# CPU_AV.net
KiCad netlist of a schematic drawn in Altium Designer
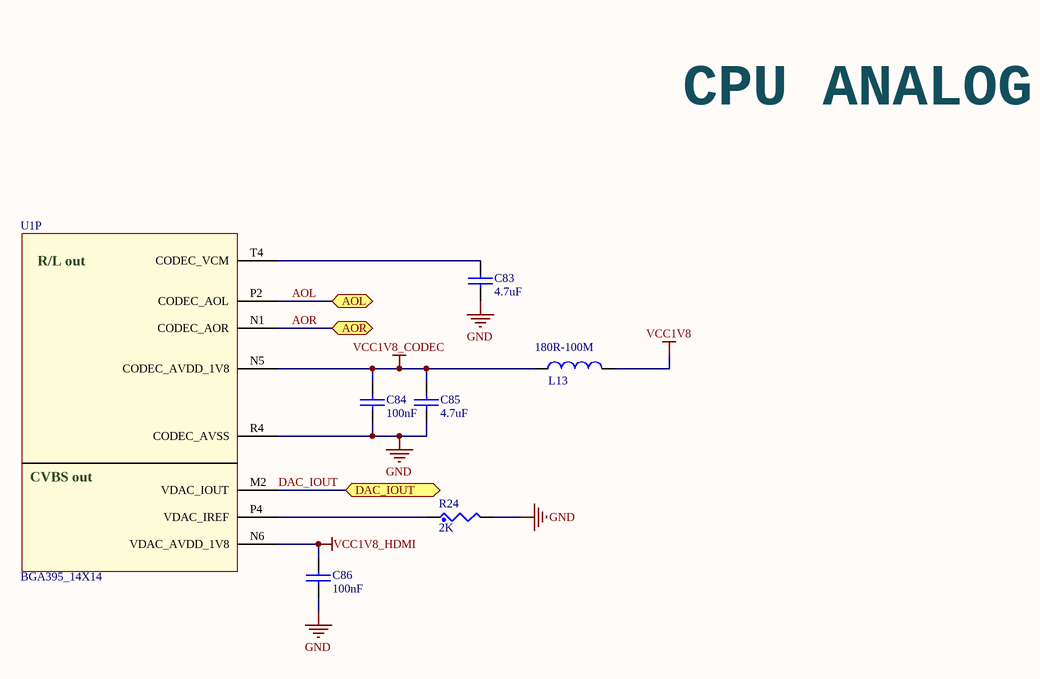
[diagram p0: CPU_AV.SchDoc]

(export (version "E")
  (design (tool "Eeschema 10.0.6"))
  (components
    (comp (ref "C83")
      (value "4.7uF")
      (footprint "0402_CC - C")
      (libsource (lib "AAR_RockChip_RK3328") (part "CAP_NP"))
    )
    (comp (ref "C84")
      (value "100nF")
      (footprint "0402_CC - C")
      (libsource (lib "AAR_RockChip_RK3328") (part "CAP_NP"))
    )
    (comp (ref "C85")
      (value "4.7uF")
      (footprint "0402_CC - C")
      (libsource (lib "AAR_RockChip_RK3328") (part "CAP_NP"))
    )
    (comp (ref "C86")
      (value "100nF")
      (footprint "0402_CC - C")
      (libsource (lib "AAR_RockChip_RK3328") (part "CAP_NP"))
    )
    (comp (ref "L13")
      (value "180R-100M")
      (footprint "0603_C_Inductor")
      (description "Fixed Inductors  TDK, By AAR")
      (libsource (lib "AAR_RockChip_RK3328") (part "INDCHIP"))
    )
    (comp (ref "R24") (value "2K") (footprint "0402_CR") (libsource (lib "AAR_RockChip_RK3328") (part "RES")))
    (comp (ref "U1")
      (value "BGA395_14X14")
      (footprint "BGA395C65P21X21_1750X1750X117")
      (description "By AAR")
      (libsource (lib "AAR_RockChip_RK3328") (part "RK3328"))
    )
  )
  (nets
    (net (code "1") (name "/AOL") (class "Default")
      (node (ref "U1") (pin "P2") (pinfunction "CODEC_AOL_P2") (pintype "passive"))
    )
    (net (code "2") (name "/AOR") (class "Default")
      (node (ref "U1") (pin "N1") (pinfunction "CODEC_AOR_N1") (pintype "passive"))
    )
    (net (code "3") (name "/DAC_IOUT") (class "Default")
      (node (ref "U1") (pin "M2") (pinfunction "VDAC_IOUT_M2") (pintype "passive"))
    )
    (net (code "4") (name "GND") (class "Default")
      (node (ref "C83") (pin "2") (pinfunction "2_2") (pintype "passive"))
      (node (ref "C84") (pin "2") (pinfunction "2_2") (pintype "passive"))
      (node (ref "C85") (pin "2") (pinfunction "2_2") (pintype "passive"))
      (node (ref "C86") (pin "2") (pinfunction "2_2") (pintype "passive"))
      (node (ref "R24") (pin "2") (pinfunction "2_2") (pintype "passive"))
      (node (ref "U1") (pin "R4") (pinfunction "CODEC_AVSS_R4") (pintype "passive"))
    )
    (net (code "5") (name "Net-(U1P-CODEC_VCM)") (class "Default")
      (node (ref "C83") (pin "1") (pinfunction "1_1") (pintype "passive"))
      (node (ref "U1") (pin "T4") (pinfunction "CODEC_VCM_T4") (pintype "passive"))
    )
    (net (code "6") (name "Net-(U1P-VDAC_IREF)") (class "Default")
      (node (ref "R24") (pin "1") (pinfunction "1_1") (pintype "passive"))
      (node (ref "U1") (pin "P4") (pinfunction "VDAC_IREF_P4") (pintype "passive"))
    )
    (net (code "7") (name "VCC1V8") (class "Default")
      (node (ref "L13") (pin "2") (pinfunction "2_2") (pintype "passive"))
    )
    (net (code "8") (name "VCC1V8_CODEC") (class "Default")
      (node (ref "C84") (pin "1") (pinfunction "1_1") (pintype "passive"))
      (node (ref "C85") (pin "1") (pinfunction "1_1") (pintype "passive"))
      (node (ref "L13") (pin "1") (pinfunction "1_1") (pintype "passive"))
      (node (ref "U1") (pin "N5") (pinfunction "CODEC_AVDD_1V8_N5") (pintype "passive"))
    )
    (net (code "9") (name "VCC1V8_HDMI") (class "Default")
      (node (ref "C86") (pin "1") (pinfunction "1_1") (pintype "passive"))
      (node (ref "U1") (pin "N6") (pinfunction "VDAC_AVDD_1V8_N6") (pintype "passive"))
    )
  )
)
